# MainBoard_RELAY.net
KiCad netlist of a schematic drawn in Altium Designer
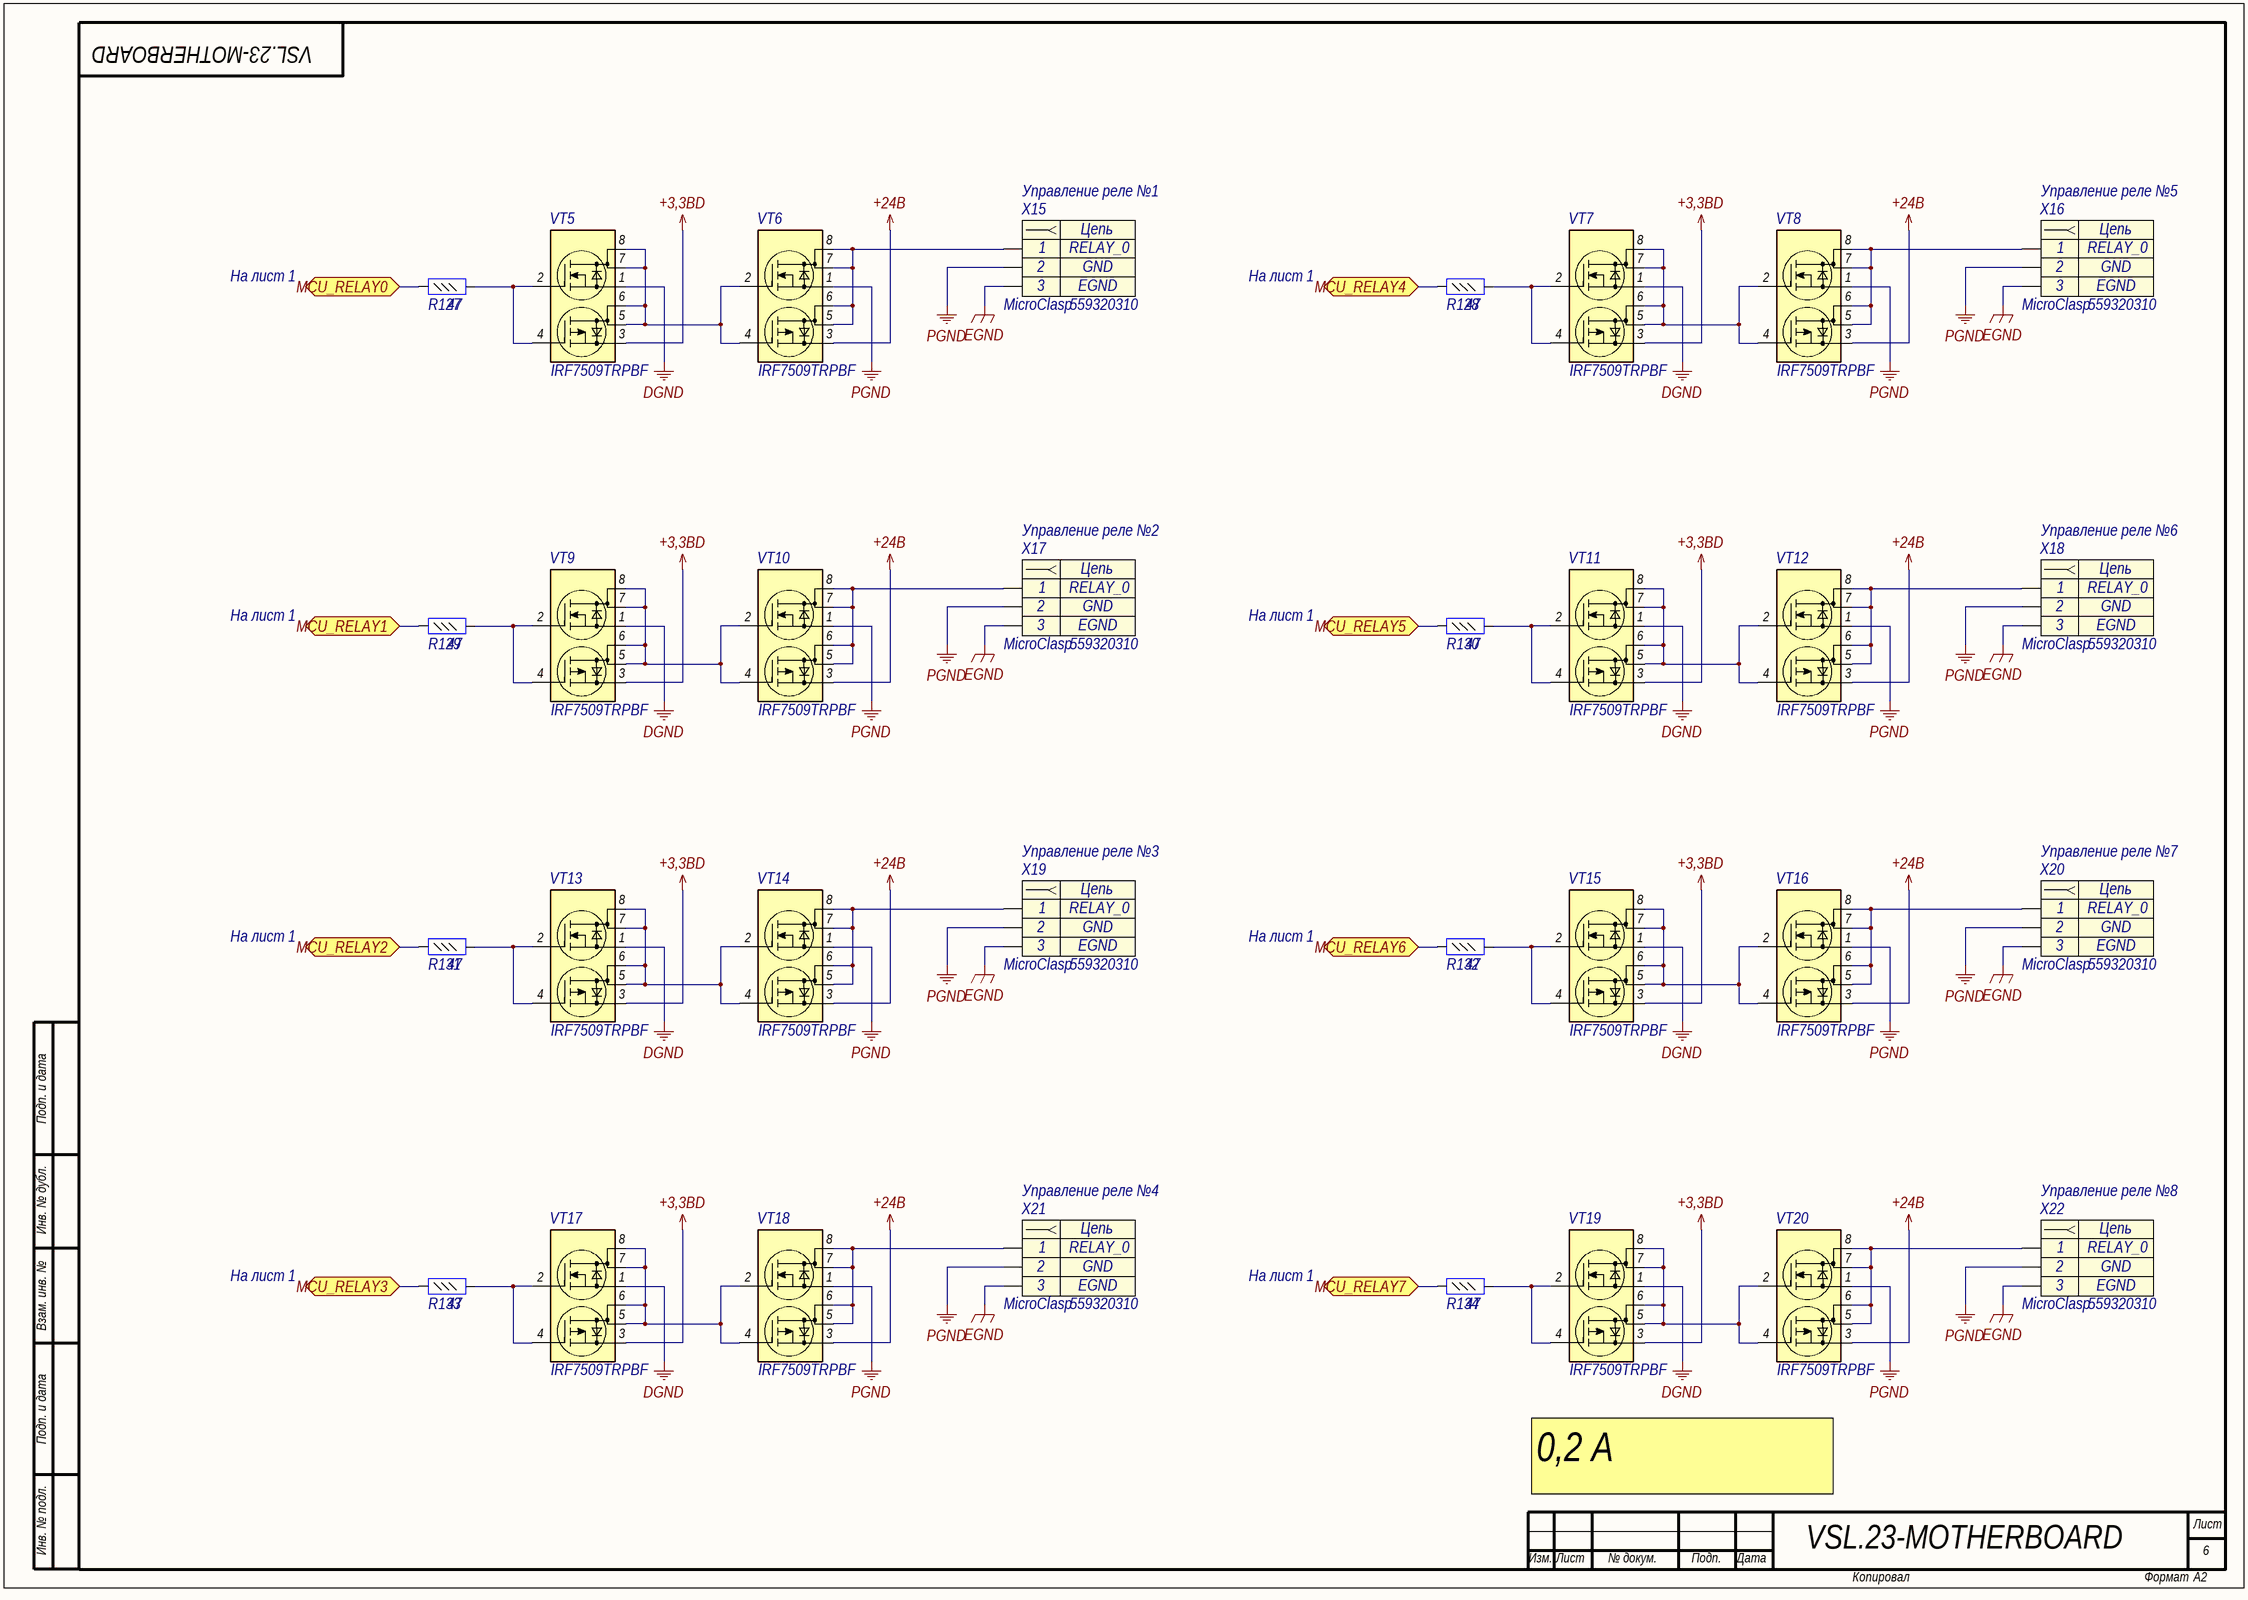
[diagram p0: MainBoard_RELAY.SchDoc]

(export (version "E")
  (design (tool "Eeschema 10.0.6"))
  (components
    (comp (ref "R127")
      (value "47")
      (footprint "R0402")
      (description "Резистор")
      (fields (field (name "PART NUMBER") "RC0402FR-0747RL") (field (name "POWER") "0,062Вт"))
      (libsource (lib "MOP44") (part "Resistor_0,062Вт"))
    )
    (comp (ref "R128")
      (value "47")
      (footprint "R0402")
      (description "Резистор")
      (fields (field (name "PART NUMBER") "RC0402FR-0747RL") (field (name "POWER") "0,062Вт"))
      (libsource (lib "MOP44") (part "Resistor_0,062Вт"))
    )
    (comp (ref "R129")
      (value "47")
      (footprint "R0402")
      (description "Резистор")
      (fields (field (name "PART NUMBER") "RC0402FR-0747RL") (field (name "POWER") "0,062Вт"))
      (libsource (lib "MOP44") (part "Resistor_0,062Вт"))
    )
    (comp (ref "R130")
      (value "47")
      (footprint "R0402")
      (description "Резистор")
      (fields (field (name "PART NUMBER") "RC0402FR-0747RL") (field (name "POWER") "0,062Вт"))
      (libsource (lib "MOP44") (part "Resistor_0,062Вт"))
    )
    (comp (ref "R131")
      (value "47")
      (footprint "R0402")
      (description "Резистор")
      (fields (field (name "PART NUMBER") "RC0402FR-0747RL") (field (name "POWER") "0,062Вт"))
      (libsource (lib "MOP44") (part "Resistor_0,062Вт"))
    )
    (comp (ref "R132")
      (value "47")
      (footprint "R0402")
      (description "Резистор")
      (fields (field (name "PART NUMBER") "RC0402FR-0747RL") (field (name "POWER") "0,062Вт"))
      (libsource (lib "MOP44") (part "Resistor_0,062Вт"))
    )
    (comp (ref "R133")
      (value "47")
      (footprint "R0402")
      (description "Резистор")
      (fields (field (name "PART NUMBER") "RC0402FR-0747RL") (field (name "POWER") "0,062Вт"))
      (libsource (lib "MOP44") (part "Resistor_0,062Вт"))
    )
    (comp (ref "R134")
      (value "47")
      (footprint "R0402")
      (description "Резистор")
      (fields (field (name "PART NUMBER") "RC0402FR-0747RL") (field (name "POWER") "0,062Вт"))
      (libsource (lib "MOP44") (part "Resistor_0,062Вт"))
    )
    (comp (ref "VT5")
      (value "IRF7509TRPBF")
      (footprint "Micro8")
      (description "Комплементарная сборка МОП")
      (fields
        (field (name "PART NUMBER") "IRF7509TRPBF")
        (field (name "MANUFACTURER") "International Rectifier")
      )
      (libsource (lib "MOP44") (part "IRF7509TRPBF"))
    )
    (comp (ref "VT6")
      (value "IRF7509TRPBF")
      (footprint "Micro8")
      (description "Комплементарная сборка МОП")
      (fields
        (field (name "PART NUMBER") "IRF7509TRPBF")
        (field (name "MANUFACTURER") "International Rectifier")
      )
      (libsource (lib "MOP44") (part "IRF7509TRPBF"))
    )
    (comp (ref "VT7")
      (value "IRF7509TRPBF")
      (footprint "Micro8")
      (description "Комплементарная сборка МОП")
      (fields
        (field (name "PART NUMBER") "IRF7509TRPBF")
        (field (name "MANUFACTURER") "International Rectifier")
      )
      (libsource (lib "MOP44") (part "IRF7509TRPBF"))
    )
    (comp (ref "VT8")
      (value "IRF7509TRPBF")
      (footprint "Micro8")
      (description "Комплементарная сборка МОП")
      (fields
        (field (name "PART NUMBER") "IRF7509TRPBF")
        (field (name "MANUFACTURER") "International Rectifier")
      )
      (libsource (lib "MOP44") (part "IRF7509TRPBF"))
    )
    (comp (ref "VT9")
      (value "IRF7509TRPBF")
      (footprint "Micro8")
      (description "Комплементарная сборка МОП")
      (fields
        (field (name "PART NUMBER") "IRF7509TRPBF")
        (field (name "MANUFACTURER") "International Rectifier")
      )
      (libsource (lib "MOP44") (part "IRF7509TRPBF"))
    )
    (comp (ref "VT10")
      (value "IRF7509TRPBF")
      (footprint "Micro8")
      (description "Комплементарная сборка МОП")
      (fields
        (field (name "PART NUMBER") "IRF7509TRPBF")
        (field (name "MANUFACTURER") "International Rectifier")
      )
      (libsource (lib "MOP44") (part "IRF7509TRPBF"))
    )
    (comp (ref "VT11")
      (value "IRF7509TRPBF")
      (footprint "Micro8")
      (description "Комплементарная сборка МОП")
      (fields
        (field (name "PART NUMBER") "IRF7509TRPBF")
        (field (name "MANUFACTURER") "International Rectifier")
      )
      (libsource (lib "MOP44") (part "IRF7509TRPBF"))
    )
    (comp (ref "VT12")
      (value "IRF7509TRPBF")
      (footprint "Micro8")
      (description "Комплементарная сборка МОП")
      (fields
        (field (name "PART NUMBER") "IRF7509TRPBF")
        (field (name "MANUFACTURER") "International Rectifier")
      )
      (libsource (lib "MOP44") (part "IRF7509TRPBF"))
    )
    (comp (ref "VT13")
      (value "IRF7509TRPBF")
      (footprint "Micro8")
      (description "Комплементарная сборка МОП")
      (fields
        (field (name "PART NUMBER") "IRF7509TRPBF")
        (field (name "MANUFACTURER") "International Rectifier")
      )
      (libsource (lib "MOP44") (part "IRF7509TRPBF"))
    )
    (comp (ref "VT14")
      (value "IRF7509TRPBF")
      (footprint "Micro8")
      (description "Комплементарная сборка МОП")
      (fields
        (field (name "PART NUMBER") "IRF7509TRPBF")
        (field (name "MANUFACTURER") "International Rectifier")
      )
      (libsource (lib "MOP44") (part "IRF7509TRPBF"))
    )
    (comp (ref "VT15")
      (value "IRF7509TRPBF")
      (footprint "Micro8")
      (description "Комплементарная сборка МОП")
      (fields
        (field (name "PART NUMBER") "IRF7509TRPBF")
        (field (name "MANUFACTURER") "International Rectifier")
      )
      (libsource (lib "MOP44") (part "IRF7509TRPBF"))
    )
    (comp (ref "VT16")
      (value "IRF7509TRPBF")
      (footprint "Micro8")
      (description "Комплементарная сборка МОП")
      (fields
        (field (name "PART NUMBER") "IRF7509TRPBF")
        (field (name "MANUFACTURER") "International Rectifier")
      )
      (libsource (lib "MOP44") (part "IRF7509TRPBF"))
    )
    (comp (ref "VT17")
      (value "IRF7509TRPBF")
      (footprint "Micro8")
      (description "Комплементарная сборка МОП")
      (fields
        (field (name "PART NUMBER") "IRF7509TRPBF")
        (field (name "MANUFACTURER") "International Rectifier")
      )
      (libsource (lib "MOP44") (part "IRF7509TRPBF"))
    )
    (comp (ref "VT18")
      (value "IRF7509TRPBF")
      (footprint "Micro8")
      (description "Комплементарная сборка МОП")
      (fields
        (field (name "PART NUMBER") "IRF7509TRPBF")
        (field (name "MANUFACTURER") "International Rectifier")
      )
      (libsource (lib "MOP44") (part "IRF7509TRPBF"))
    )
    (comp (ref "VT19")
      (value "IRF7509TRPBF")
      (footprint "Micro8")
      (description "Комплементарная сборка МОП")
      (fields
        (field (name "PART NUMBER") "IRF7509TRPBF")
        (field (name "MANUFACTURER") "International Rectifier")
      )
      (libsource (lib "MOP44") (part "IRF7509TRPBF"))
    )
    (comp (ref "VT20")
      (value "IRF7509TRPBF")
      (footprint "Micro8")
      (description "Комплементарная сборка МОП")
      (fields
        (field (name "PART NUMBER") "IRF7509TRPBF")
        (field (name "MANUFACTURER") "International Rectifier")
      )
      (libsource (lib "MOP44") (part "IRF7509TRPBF"))
    )
    (comp (ref "X15")
      (value "Управление реле №1")
      (footprint "MOLEX_559320310")
      (description "Разъем - 3 конт. розетка")
      (fields (field (name "PART NAME") "MicroClasp") (field (name "PART NUMBER") "559320310"))
      (libsource (lib "MOP44") (part "Header_3_sct"))
    )
    (comp (ref "X16")
      (value "Управление реле №5")
      (footprint "MOLEX_559320310")
      (description "Разъем - 3 конт. розетка")
      (fields (field (name "PART NAME") "MicroClasp") (field (name "PART NUMBER") "559320310"))
      (libsource (lib "MOP44") (part "Header_3_sct"))
    )
    (comp (ref "X17")
      (value "Управление реле №2")
      (footprint "MOLEX_559320310")
      (description "Разъем - 3 конт. розетка")
      (fields (field (name "PART NAME") "MicroClasp") (field (name "PART NUMBER") "559320310"))
      (libsource (lib "MOP44") (part "Header_3_sct"))
    )
    (comp (ref "X18")
      (value "Управление реле №6")
      (footprint "MOLEX_559320310")
      (description "Разъем - 3 конт. розетка")
      (fields (field (name "PART NAME") "MicroClasp") (field (name "PART NUMBER") "559320310"))
      (libsource (lib "MOP44") (part "Header_3_sct"))
    )
    (comp (ref "X19")
      (value "Управление реле №3")
      (footprint "MOLEX_559320310")
      (description "Разъем - 3 конт. розетка")
      (fields (field (name "PART NAME") "MicroClasp") (field (name "PART NUMBER") "559320310"))
      (libsource (lib "MOP44") (part "Header_3_sct"))
    )
    (comp (ref "X20")
      (value "Управление реле №7")
      (footprint "MOLEX_559320310")
      (description "Разъем - 3 конт. розетка")
      (fields (field (name "PART NAME") "MicroClasp") (field (name "PART NUMBER") "559320310"))
      (libsource (lib "MOP44") (part "Header_3_sct"))
    )
    (comp (ref "X21")
      (value "Управление реле №4")
      (footprint "MOLEX_559320310")
      (description "Разъем - 3 конт. розетка")
      (fields (field (name "PART NAME") "MicroClasp") (field (name "PART NUMBER") "559320310"))
      (libsource (lib "MOP44") (part "Header_3_sct"))
    )
    (comp (ref "X22")
      (value "Управление реле №8")
      (footprint "MOLEX_559320310")
      (description "Разъем - 3 конт. розетка")
      (fields (field (name "PART NAME") "MicroClasp") (field (name "PART NUMBER") "559320310"))
      (libsource (lib "MOP44") (part "Header_3_sct"))
    )
  )
  (nets
    (net (code "1") (name "+3,3BD") (class "Default")
      (node (ref "VT11") (pin "3") (pinfunction "S2_3") (pintype "passive"))
      (node (ref "VT13") (pin "3") (pinfunction "S2_3") (pintype "passive"))
      (node (ref "VT15") (pin "3") (pinfunction "S2_3") (pintype "passive"))
      (node (ref "VT17") (pin "3") (pinfunction "S2_3") (pintype "passive"))
      (node (ref "VT19") (pin "3") (pinfunction "S2_3") (pintype "passive"))
      (node (ref "VT5") (pin "3") (pinfunction "S2_3") (pintype "passive"))
      (node (ref "VT7") (pin "3") (pinfunction "S2_3") (pintype "passive"))
      (node (ref "VT9") (pin "3") (pinfunction "S2_3") (pintype "passive"))
    )
    (net (code "2") (name "+24B") (class "Default")
      (node (ref "VT10") (pin "3") (pinfunction "S2_3") (pintype "passive"))
      (node (ref "VT12") (pin "3") (pinfunction "S2_3") (pintype "passive"))
      (node (ref "VT14") (pin "3") (pinfunction "S2_3") (pintype "passive"))
      (node (ref "VT16") (pin "3") (pinfunction "S2_3") (pintype "passive"))
      (node (ref "VT18") (pin "3") (pinfunction "S2_3") (pintype "passive"))
      (node (ref "VT20") (pin "3") (pinfunction "S2_3") (pintype "passive"))
      (node (ref "VT6") (pin "3") (pinfunction "S2_3") (pintype "passive"))
      (node (ref "VT8") (pin "3") (pinfunction "S2_3") (pintype "passive"))
    )
    (net (code "3") (name "/MCU_RELAY0") (class "Default")
      (node (ref "R127") (pin "1") (pinfunction "1_1") (pintype "passive"))
    )
    (net (code "4") (name "/MCU_RELAY1") (class "Default")
      (node (ref "R129") (pin "1") (pinfunction "1_1") (pintype "passive"))
    )
    (net (code "5") (name "/MCU_RELAY2") (class "Default")
      (node (ref "R131") (pin "1") (pinfunction "1_1") (pintype "passive"))
    )
    (net (code "6") (name "/MCU_RELAY3") (class "Default")
      (node (ref "R133") (pin "1") (pinfunction "1_1") (pintype "passive"))
    )
    (net (code "7") (name "/MCU_RELAY4") (class "Default")
      (node (ref "R128") (pin "1") (pinfunction "1_1") (pintype "passive"))
    )
    (net (code "8") (name "/MCU_RELAY5") (class "Default")
      (node (ref "R130") (pin "1") (pinfunction "1_1") (pintype "passive"))
    )
    (net (code "9") (name "/MCU_RELAY6") (class "Default")
      (node (ref "R132") (pin "1") (pinfunction "1_1") (pintype "passive"))
    )
    (net (code "10") (name "/MCU_RELAY7") (class "Default")
      (node (ref "R134") (pin "1") (pinfunction "1_1") (pintype "passive"))
    )
    (net (code "11") (name "DGND") (class "Default")
      (node (ref "VT11") (pin "1") (pinfunction "S1_1") (pintype "passive"))
      (node (ref "VT13") (pin "1") (pinfunction "S1_1") (pintype "passive"))
      (node (ref "VT15") (pin "1") (pinfunction "S1_1") (pintype "passive"))
      (node (ref "VT17") (pin "1") (pinfunction "S1_1") (pintype "passive"))
      (node (ref "VT19") (pin "1") (pinfunction "S1_1") (pintype "passive"))
      (node (ref "VT5") (pin "1") (pinfunction "S1_1") (pintype "passive"))
      (node (ref "VT7") (pin "1") (pinfunction "S1_1") (pintype "passive"))
      (node (ref "VT9") (pin "1") (pinfunction "S1_1") (pintype "passive"))
    )
    (net (code "12") (name "EGND") (class "Default")
      (node (ref "X15") (pin "3") (pinfunction "3_3") (pintype "passive"))
      (node (ref "X16") (pin "3") (pinfunction "3_3") (pintype "passive"))
      (node (ref "X17") (pin "3") (pinfunction "3_3") (pintype "passive"))
      (node (ref "X18") (pin "3") (pinfunction "3_3") (pintype "passive"))
      (node (ref "X19") (pin "3") (pinfunction "3_3") (pintype "passive"))
      (node (ref "X20") (pin "3") (pinfunction "3_3") (pintype "passive"))
      (node (ref "X21") (pin "3") (pinfunction "3_3") (pintype "passive"))
      (node (ref "X22") (pin "3") (pinfunction "3_3") (pintype "passive"))
    )
    (net (code "13") (name "Net-(VT5-G1)") (class "Default")
      (node (ref "R127") (pin "2") (pinfunction "2_2") (pintype "passive"))
      (node (ref "VT5") (pin "2") (pinfunction "G1_2") (pintype "passive"))
      (node (ref "VT5") (pin "4") (pinfunction "G2_4") (pintype "passive"))
    )
    (net (code "14") (name "Net-(VT6-D1-Pad7)") (class "Default")
      (node (ref "VT6") (pin "5") (pinfunction "D2_5") (pintype "passive"))
      (node (ref "VT6") (pin "6") (pinfunction "D2_6") (pintype "passive"))
      (node (ref "VT6") (pin "7") (pinfunction "D1_7") (pintype "passive"))
      (node (ref "VT6") (pin "8") (pinfunction "D1_8") (pintype "passive"))
      (node (ref "X15") (pin "1") (pinfunction "1_1") (pintype "passive"))
    )
    (net (code "15") (name "Net-(VT6-G1)") (class "Default")
      (node (ref "VT5") (pin "5") (pinfunction "D2_5") (pintype "passive"))
      (node (ref "VT5") (pin "6") (pinfunction "D2_6") (pintype "passive"))
      (node (ref "VT5") (pin "7") (pinfunction "D1_7") (pintype "passive"))
      (node (ref "VT5") (pin "8") (pinfunction "D1_8") (pintype "passive"))
      (node (ref "VT6") (pin "2") (pinfunction "G1_2") (pintype "passive"))
      (node (ref "VT6") (pin "4") (pinfunction "G2_4") (pintype "passive"))
    )
    (net (code "16") (name "Net-(VT7-G1)") (class "Default")
      (node (ref "R128") (pin "2") (pinfunction "2_2") (pintype "passive"))
      (node (ref "VT7") (pin "2") (pinfunction "G1_2") (pintype "passive"))
      (node (ref "VT7") (pin "4") (pinfunction "G2_4") (pintype "passive"))
    )
    (net (code "17") (name "Net-(VT8-D1-Pad7)") (class "Default")
      (node (ref "VT8") (pin "5") (pinfunction "D2_5") (pintype "passive"))
      (node (ref "VT8") (pin "6") (pinfunction "D2_6") (pintype "passive"))
      (node (ref "VT8") (pin "7") (pinfunction "D1_7") (pintype "passive"))
      (node (ref "VT8") (pin "8") (pinfunction "D1_8") (pintype "passive"))
      (node (ref "X16") (pin "1") (pinfunction "1_1") (pintype "passive"))
    )
    (net (code "18") (name "Net-(VT8-G1)") (class "Default")
      (node (ref "VT7") (pin "5") (pinfunction "D2_5") (pintype "passive"))
      (node (ref "VT7") (pin "6") (pinfunction "D2_6") (pintype "passive"))
      (node (ref "VT7") (pin "7") (pinfunction "D1_7") (pintype "passive"))
      (node (ref "VT7") (pin "8") (pinfunction "D1_8") (pintype "passive"))
      (node (ref "VT8") (pin "2") (pinfunction "G1_2") (pintype "passive"))
      (node (ref "VT8") (pin "4") (pinfunction "G2_4") (pintype "passive"))
    )
    (net (code "19") (name "Net-(VT9-G1)") (class "Default")
      (node (ref "R129") (pin "2") (pinfunction "2_2") (pintype "passive"))
      (node (ref "VT9") (pin "2") (pinfunction "G1_2") (pintype "passive"))
      (node (ref "VT9") (pin "4") (pinfunction "G2_4") (pintype "passive"))
    )
    (net (code "20") (name "Net-(VT10-D1-Pad7)") (class "Default")
      (node (ref "VT10") (pin "5") (pinfunction "D2_5") (pintype "passive"))
      (node (ref "VT10") (pin "6") (pinfunction "D2_6") (pintype "passive"))
      (node (ref "VT10") (pin "7") (pinfunction "D1_7") (pintype "passive"))
      (node (ref "VT10") (pin "8") (pinfunction "D1_8") (pintype "passive"))
      (node (ref "X17") (pin "1") (pinfunction "1_1") (pintype "passive"))
    )
    (net (code "21") (name "Net-(VT10-G1)") (class "Default")
      (node (ref "VT10") (pin "2") (pinfunction "G1_2") (pintype "passive"))
      (node (ref "VT10") (pin "4") (pinfunction "G2_4") (pintype "passive"))
      (node (ref "VT9") (pin "5") (pinfunction "D2_5") (pintype "passive"))
      (node (ref "VT9") (pin "6") (pinfunction "D2_6") (pintype "passive"))
      (node (ref "VT9") (pin "7") (pinfunction "D1_7") (pintype "passive"))
      (node (ref "VT9") (pin "8") (pinfunction "D1_8") (pintype "passive"))
    )
    (net (code "22") (name "Net-(VT11-G1)") (class "Default")
      (node (ref "R130") (pin "2") (pinfunction "2_2") (pintype "passive"))
      (node (ref "VT11") (pin "2") (pinfunction "G1_2") (pintype "passive"))
      (node (ref "VT11") (pin "4") (pinfunction "G2_4") (pintype "passive"))
    )
    (net (code "23") (name "Net-(VT12-D1-Pad7)") (class "Default")
      (node (ref "VT12") (pin "5") (pinfunction "D2_5") (pintype "passive"))
      (node (ref "VT12") (pin "6") (pinfunction "D2_6") (pintype "passive"))
      (node (ref "VT12") (pin "7") (pinfunction "D1_7") (pintype "passive"))
      (node (ref "VT12") (pin "8") (pinfunction "D1_8") (pintype "passive"))
      (node (ref "X18") (pin "1") (pinfunction "1_1") (pintype "passive"))
    )
    (net (code "24") (name "Net-(VT12-G1)") (class "Default")
      (node (ref "VT11") (pin "5") (pinfunction "D2_5") (pintype "passive"))
      (node (ref "VT11") (pin "6") (pinfunction "D2_6") (pintype "passive"))
      (node (ref "VT11") (pin "7") (pinfunction "D1_7") (pintype "passive"))
      (node (ref "VT11") (pin "8") (pinfunction "D1_8") (pintype "passive"))
      (node (ref "VT12") (pin "2") (pinfunction "G1_2") (pintype "passive"))
      (node (ref "VT12") (pin "4") (pinfunction "G2_4") (pintype "passive"))
    )
    (net (code "25") (name "Net-(VT13-G1)") (class "Default")
      (node (ref "R131") (pin "2") (pinfunction "2_2") (pintype "passive"))
      (node (ref "VT13") (pin "2") (pinfunction "G1_2") (pintype "passive"))
      (node (ref "VT13") (pin "4") (pinfunction "G2_4") (pintype "passive"))
    )
    (net (code "26") (name "Net-(VT14-D1-Pad7)") (class "Default")
      (node (ref "VT14") (pin "5") (pinfunction "D2_5") (pintype "passive"))
      (node (ref "VT14") (pin "6") (pinfunction "D2_6") (pintype "passive"))
      (node (ref "VT14") (pin "7") (pinfunction "D1_7") (pintype "passive"))
      (node (ref "VT14") (pin "8") (pinfunction "D1_8") (pintype "passive"))
      (node (ref "X19") (pin "1") (pinfunction "1_1") (pintype "passive"))
    )
    (net (code "27") (name "Net-(VT14-G1)") (class "Default")
      (node (ref "VT13") (pin "5") (pinfunction "D2_5") (pintype "passive"))
      (node (ref "VT13") (pin "6") (pinfunction "D2_6") (pintype "passive"))
      (node (ref "VT13") (pin "7") (pinfunction "D1_7") (pintype "passive"))
      (node (ref "VT13") (pin "8") (pinfunction "D1_8") (pintype "passive"))
      (node (ref "VT14") (pin "2") (pinfunction "G1_2") (pintype "passive"))
      (node (ref "VT14") (pin "4") (pinfunction "G2_4") (pintype "passive"))
    )
    (net (code "28") (name "Net-(VT15-G1)") (class "Default")
      (node (ref "R132") (pin "2") (pinfunction "2_2") (pintype "passive"))
      (node (ref "VT15") (pin "2") (pinfunction "G1_2") (pintype "passive"))
      (node (ref "VT15") (pin "4") (pinfunction "G2_4") (pintype "passive"))
    )
    (net (code "29") (name "Net-(VT16-D1-Pad7)") (class "Default")
      (node (ref "VT16") (pin "5") (pinfunction "D2_5") (pintype "passive"))
      (node (ref "VT16") (pin "6") (pinfunction "D2_6") (pintype "passive"))
      (node (ref "VT16") (pin "7") (pinfunction "D1_7") (pintype "passive"))
      (node (ref "VT16") (pin "8") (pinfunction "D1_8") (pintype "passive"))
      (node (ref "X20") (pin "1") (pinfunction "1_1") (pintype "passive"))
    )
    (net (code "30") (name "Net-(VT16-G1)") (class "Default")
      (node (ref "VT15") (pin "5") (pinfunction "D2_5") (pintype "passive"))
      (node (ref "VT15") (pin "6") (pinfunction "D2_6") (pintype "passive"))
      (node (ref "VT15") (pin "7") (pinfunction "D1_7") (pintype "passive"))
      (node (ref "VT15") (pin "8") (pinfunction "D1_8") (pintype "passive"))
      (node (ref "VT16") (pin "2") (pinfunction "G1_2") (pintype "passive"))
      (node (ref "VT16") (pin "4") (pinfunction "G2_4") (pintype "passive"))
    )
    (net (code "31") (name "Net-(VT17-G1)") (class "Default")
      (node (ref "R133") (pin "2") (pinfunction "2_2") (pintype "passive"))
      (node (ref "VT17") (pin "2") (pinfunction "G1_2") (pintype "passive"))
      (node (ref "VT17") (pin "4") (pinfunction "G2_4") (pintype "passive"))
    )
    (net (code "32") (name "Net-(VT18-D1-Pad7)") (class "Default")
      (node (ref "VT18") (pin "5") (pinfunction "D2_5") (pintype "passive"))
      (node (ref "VT18") (pin "6") (pinfunction "D2_6") (pintype "passive"))
      (node (ref "VT18") (pin "7") (pinfunction "D1_7") (pintype "passive"))
      (node (ref "VT18") (pin "8") (pinfunction "D1_8") (pintype "passive"))
      (node (ref "X21") (pin "1") (pinfunction "1_1") (pintype "passive"))
    )
    (net (code "33") (name "Net-(VT18-G1)") (class "Default")
      (node (ref "VT17") (pin "5") (pinfunction "D2_5") (pintype "passive"))
      (node (ref "VT17") (pin "6") (pinfunction "D2_6") (pintype "passive"))
      (node (ref "VT17") (pin "7") (pinfunction "D1_7") (pintype "passive"))
      (node (ref "VT17") (pin "8") (pinfunction "D1_8") (pintype "passive"))
      (node (ref "VT18") (pin "2") (pinfunction "G1_2") (pintype "passive"))
      (node (ref "VT18") (pin "4") (pinfunction "G2_4") (pintype "passive"))
    )
    (net (code "34") (name "Net-(VT19-G1)") (class "Default")
      (node (ref "R134") (pin "2") (pinfunction "2_2") (pintype "passive"))
      (node (ref "VT19") (pin "2") (pinfunction "G1_2") (pintype "passive"))
      (node (ref "VT19") (pin "4") (pinfunction "G2_4") (pintype "passive"))
    )
    (net (code "35") (name "Net-(VT20-D1-Pad7)") (class "Default")
      (node (ref "VT20") (pin "5") (pinfunction "D2_5") (pintype "passive"))
      (node (ref "VT20") (pin "6") (pinfunction "D2_6") (pintype "passive"))
      (node (ref "VT20") (pin "7") (pinfunction "D1_7") (pintype "passive"))
      (node (ref "VT20") (pin "8") (pinfunction "D1_8") (pintype "passive"))
      (node (ref "X22") (pin "1") (pinfunction "1_1") (pintype "passive"))
    )
    (net (code "36") (name "Net-(VT20-G1)") (class "Default")
      (node (ref "VT19") (pin "5") (pinfunction "D2_5") (pintype "passive"))
      (node (ref "VT19") (pin "6") (pinfunction "D2_6") (pintype "passive"))
      (node (ref "VT19") (pin "7") (pinfunction "D1_7") (pintype "passive"))
      (node (ref "VT19") (pin "8") (pinfunction "D1_8") (pintype "passive"))
      (node (ref "VT20") (pin "2") (pinfunction "G1_2") (pintype "passive"))
      (node (ref "VT20") (pin "4") (pinfunction "G2_4") (pintype "passive"))
    )
    (net (code "37") (name "PGND") (class "Default")
      (node (ref "VT10") (pin "1") (pinfunction "S1_1") (pintype "passive"))
      (node (ref "VT12") (pin "1") (pinfunction "S1_1") (pintype "passive"))
      (node (ref "VT14") (pin "1") (pinfunction "S1_1") (pintype "passive"))
      (node (ref "VT16") (pin "1") (pinfunction "S1_1") (pintype "passive"))
      (node (ref "VT18") (pin "1") (pinfunction "S1_1") (pintype "passive"))
      (node (ref "VT20") (pin "1") (pinfunction "S1_1") (pintype "passive"))
      (node (ref "VT6") (pin "1") (pinfunction "S1_1") (pintype "passive"))
      (node (ref "VT8") (pin "1") (pinfunction "S1_1") (pintype "passive"))
      (node (ref "X15") (pin "2") (pinfunction "2_2") (pintype "passive"))
      (node (ref "X16") (pin "2") (pinfunction "2_2") (pintype "passive"))
      (node (ref "X17") (pin "2") (pinfunction "2_2") (pintype "passive"))
      (node (ref "X18") (pin "2") (pinfunction "2_2") (pintype "passive"))
      (node (ref "X19") (pin "2") (pinfunction "2_2") (pintype "passive"))
      (node (ref "X20") (pin "2") (pinfunction "2_2") (pintype "passive"))
      (node (ref "X21") (pin "2") (pinfunction "2_2") (pintype "passive"))
      (node (ref "X22") (pin "2") (pinfunction "2_2") (pintype "passive"))
    )
  )
)
